# 401_GridPos4.net
KiCad netlist of a schematic drawn in Altium Designer
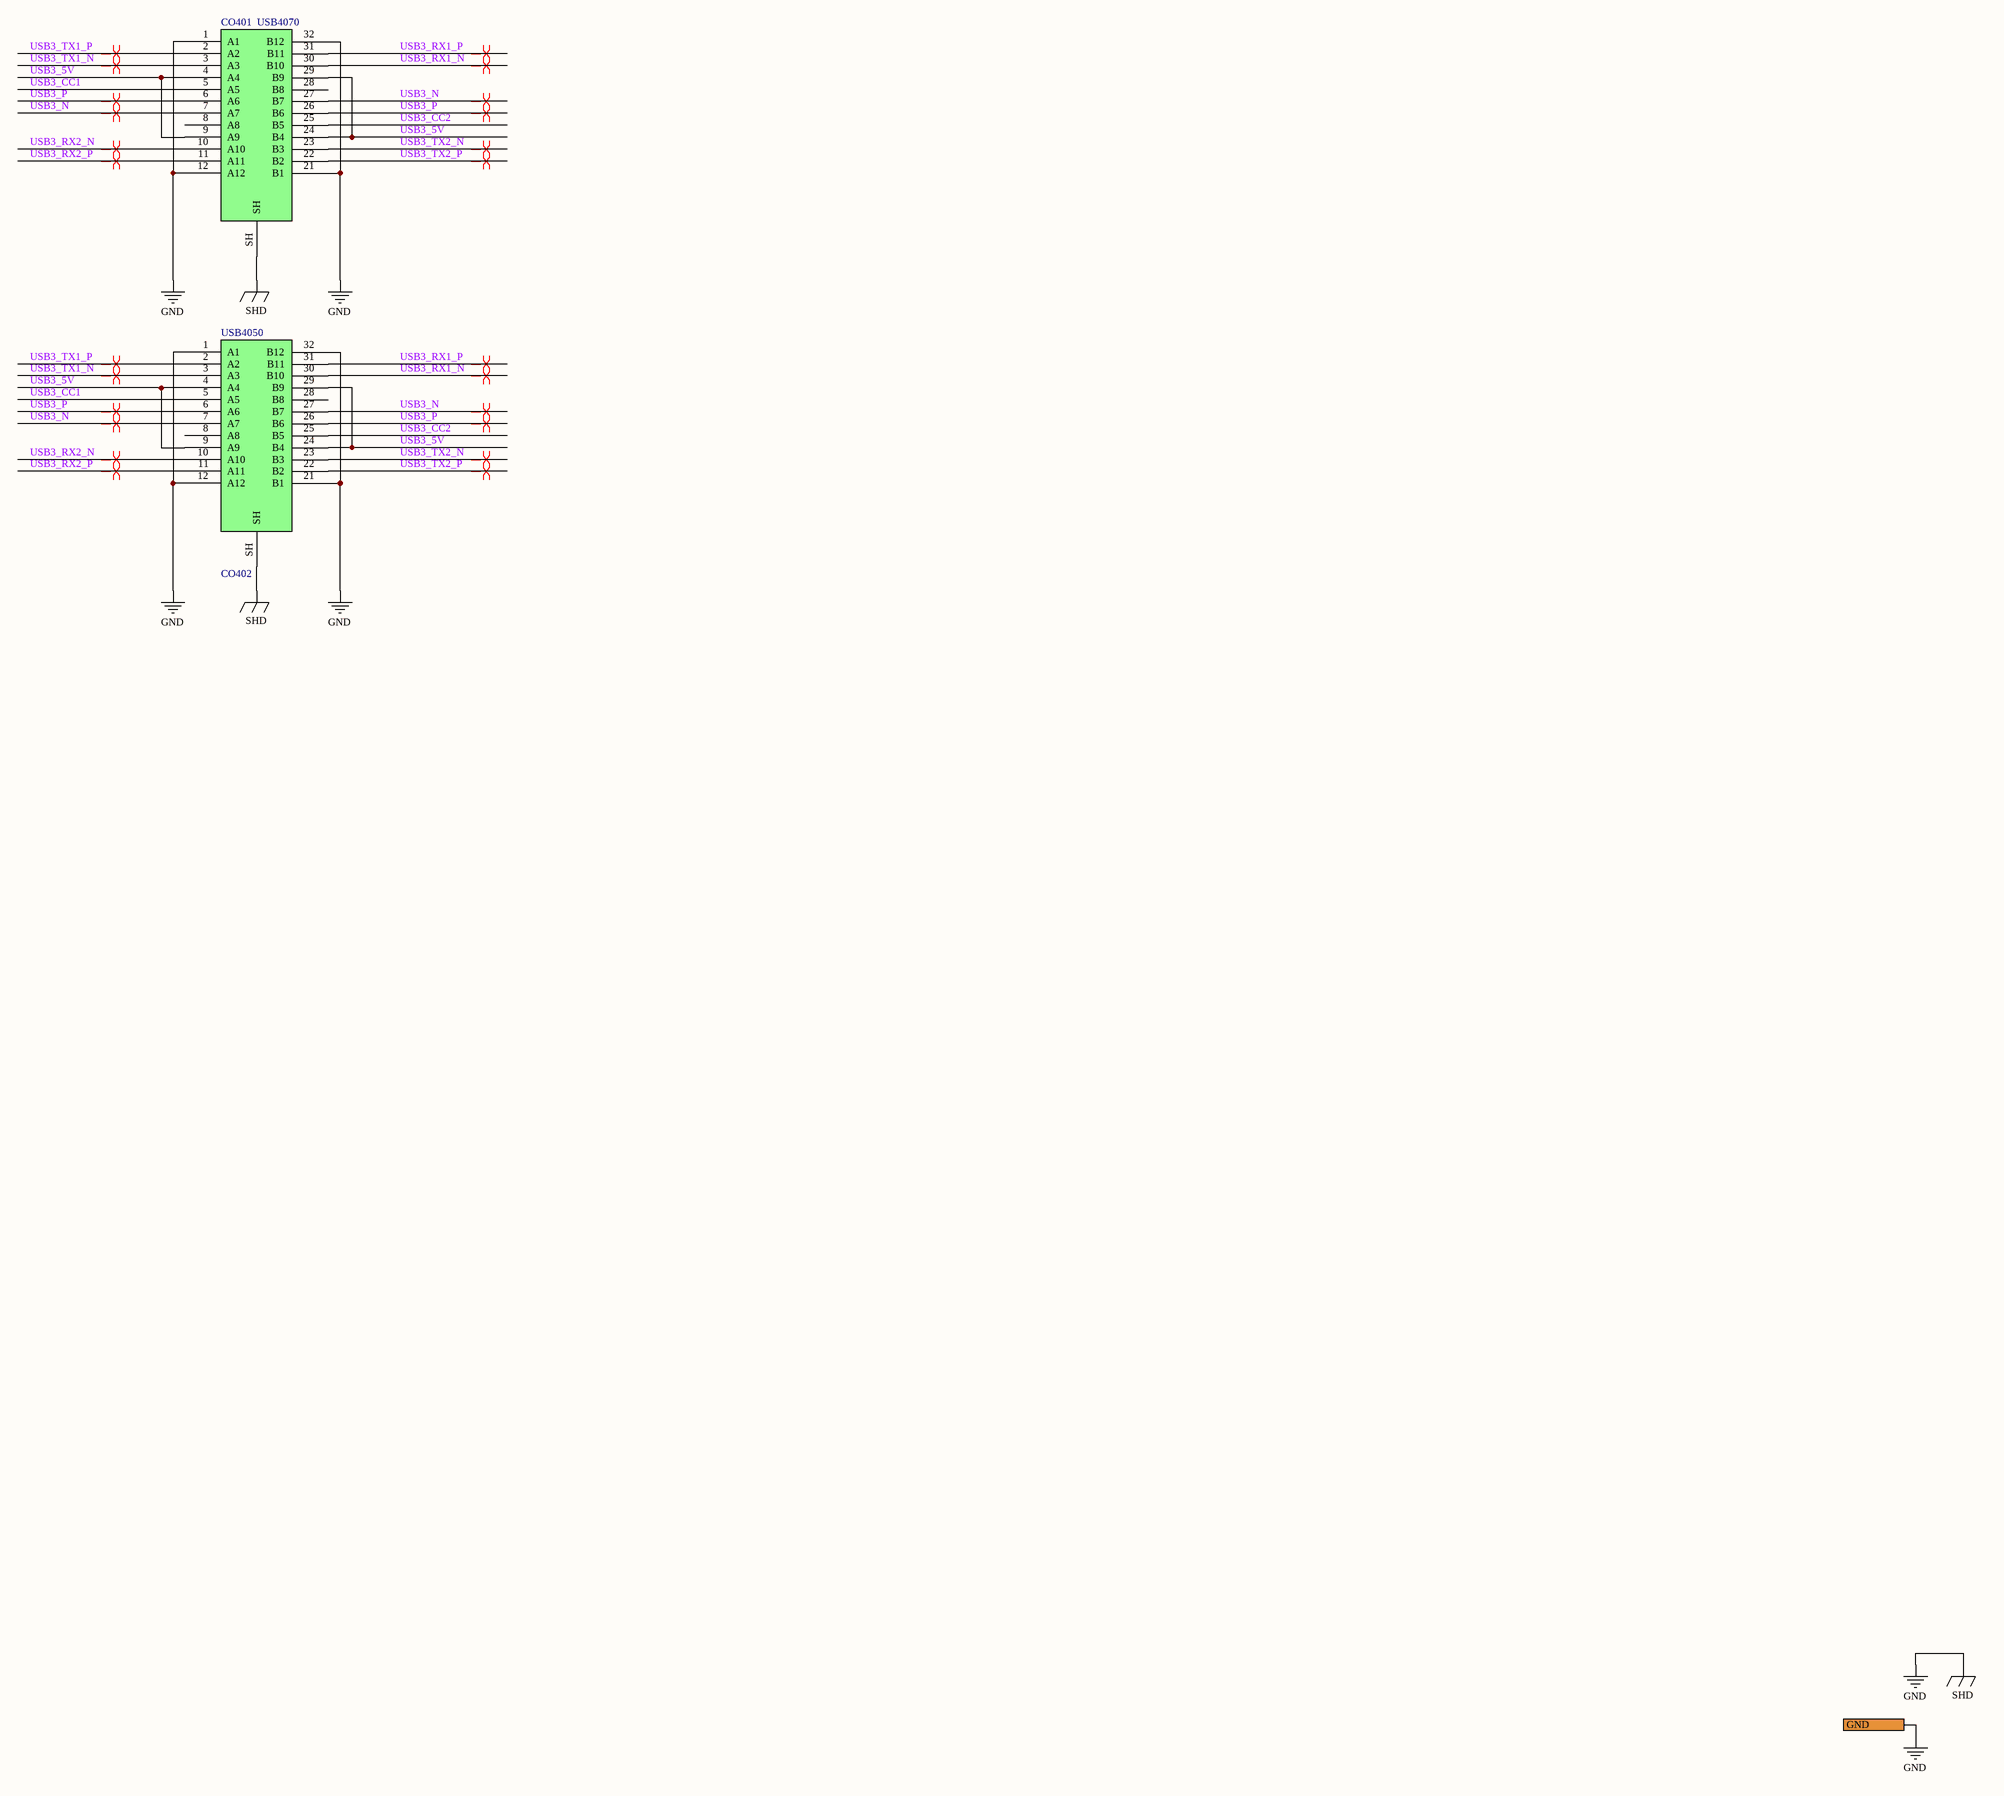
[diagram p0: 401_GridPos4.SchDoc]

(export (version "E")
  (design (tool "Eeschema 10.0.6"))
  (components
    (comp (ref "CO401")
      (value "USB4070")
      (footprint "USB4070-30-C")
      (description "USB4070-30-C")
      (fields (field (name "REFVAL") "USB4070") (field (name "PART NUMBER") "CO0021"))
      (libsource (lib "GTS_Database") (part "USB-CC"))
    )
    (comp (ref "CO402")
      (value "USB4050")
      (footprint "USB4050-30-A")
      (description "USB C connector Receptacle Horizontal")
      (fields
        (field (name "REFVAL") "USB4050")
        (field (name "PART NUMBER") "CO0039")
        (field (name "MANFACTPART") "USB4050-30-A")
      )
      (libsource (lib "") (part "USB-CC_1"))
    )
  )
  (nets
    (net (code "1") (name "/USB3_5V") (class "Default")
      (node (ref "CO401") (pin "24") (pinfunction "B4_24") (pintype "passive"))
      (node (ref "CO401") (pin "29") (pinfunction "B9_29") (pintype "passive"))
      (node (ref "CO401") (pin "4") (pinfunction "A4_4") (pintype "passive"))
      (node (ref "CO401") (pin "9") (pinfunction "A9_9") (pintype "passive"))
      (node (ref "CO402") (pin "24") (pinfunction "B4_24") (pintype "passive"))
      (node (ref "CO402") (pin "29") (pinfunction "B9_29") (pintype "passive"))
      (node (ref "CO402") (pin "4") (pinfunction "A4_4") (pintype "passive"))
      (node (ref "CO402") (pin "9") (pinfunction "A9_9") (pintype "passive"))
    )
    (net (code "2") (name "/USB3_CC1") (class "Default")
      (node (ref "CO401") (pin "5") (pinfunction "A5_5") (pintype "passive"))
      (node (ref "CO402") (pin "5") (pinfunction "A5_5") (pintype "passive"))
    )
    (net (code "3") (name "/USB3_CC2") (class "Default")
      (node (ref "CO401") (pin "25") (pinfunction "B5_25") (pintype "passive"))
      (node (ref "CO402") (pin "25") (pinfunction "B5_25") (pintype "passive"))
    )
    (net (code "4") (name "/USB3_N") (class "Default")
      (node (ref "CO401") (pin "27") (pinfunction "B7_27") (pintype "passive"))
      (node (ref "CO401") (pin "7") (pinfunction "A7_7") (pintype "passive"))
      (node (ref "CO402") (pin "27") (pinfunction "B7_27") (pintype "passive"))
      (node (ref "CO402") (pin "7") (pinfunction "A7_7") (pintype "passive"))
    )
    (net (code "5") (name "/USB3_P") (class "Default")
      (node (ref "CO401") (pin "26") (pinfunction "B6_26") (pintype "passive"))
      (node (ref "CO401") (pin "6") (pinfunction "A6_6") (pintype "passive"))
      (node (ref "CO402") (pin "26") (pinfunction "B6_26") (pintype "passive"))
      (node (ref "CO402") (pin "6") (pinfunction "A6_6") (pintype "passive"))
    )
    (net (code "6") (name "/USB3_RX1_N") (class "Default")
      (node (ref "CO401") (pin "30") (pinfunction "B10_30") (pintype "passive"))
      (node (ref "CO402") (pin "30") (pinfunction "B10_30") (pintype "passive"))
    )
    (net (code "7") (name "/USB3_RX1_P") (class "Default")
      (node (ref "CO401") (pin "31") (pinfunction "B11_31") (pintype "passive"))
      (node (ref "CO402") (pin "31") (pinfunction "B11_31") (pintype "passive"))
    )
    (net (code "8") (name "/USB3_RX2_N") (class "Default")
      (node (ref "CO401") (pin "10") (pinfunction "A10_10") (pintype "passive"))
      (node (ref "CO402") (pin "10") (pinfunction "A10_10") (pintype "passive"))
    )
    (net (code "9") (name "/USB3_RX2_P") (class "Default")
      (node (ref "CO401") (pin "11") (pinfunction "A11_11") (pintype "passive"))
      (node (ref "CO402") (pin "11") (pinfunction "A11_11") (pintype "passive"))
    )
    (net (code "10") (name "/USB3_TX1_N") (class "Default")
      (node (ref "CO401") (pin "3") (pinfunction "A3_3") (pintype "passive"))
      (node (ref "CO402") (pin "3") (pinfunction "A3_3") (pintype "passive"))
    )
    (net (code "11") (name "/USB3_TX1_P") (class "Default")
      (node (ref "CO401") (pin "2") (pinfunction "A2_2") (pintype "passive"))
      (node (ref "CO402") (pin "2") (pinfunction "A2_2") (pintype "passive"))
    )
    (net (code "12") (name "/USB3_TX2_N") (class "Default")
      (node (ref "CO401") (pin "23") (pinfunction "B3_23") (pintype "passive"))
      (node (ref "CO402") (pin "23") (pinfunction "B3_23") (pintype "passive"))
    )
    (net (code "13") (name "/USB3_TX2_P") (class "Default")
      (node (ref "CO401") (pin "22") (pinfunction "B2_22") (pintype "passive"))
      (node (ref "CO402") (pin "22") (pinfunction "B2_22") (pintype "passive"))
    )
    (net (code "14") (name "GND") (class "Default")
      (node (ref "CO401") (pin "1") (pinfunction "A1_1") (pintype "passive"))
      (node (ref "CO401") (pin "12") (pinfunction "A12_12") (pintype "passive"))
      (node (ref "CO401") (pin "21") (pinfunction "B1_21") (pintype "passive"))
      (node (ref "CO401") (pin "32") (pinfunction "B12_32") (pintype "passive"))
      (node (ref "CO401") (pin "SH") (pinfunction "SH_SH") (pintype "power_in"))
      (node (ref "CO402") (pin "1") (pinfunction "A1_1") (pintype "passive"))
      (node (ref "CO402") (pin "12") (pinfunction "A12_12") (pintype "passive"))
      (node (ref "CO402") (pin "21") (pinfunction "B1_21") (pintype "passive"))
      (node (ref "CO402") (pin "32") (pinfunction "B12_32") (pintype "passive"))
      (node (ref "CO402") (pin "SH") (pinfunction "SH_SH") (pintype "power_in"))
    )
    (net (code "15") (name "unconnected-(CO401-A8-Pad8)") (class "Default")
      (node (ref "CO401") (pin "8") (pinfunction "A8_8") (pintype "passive"))
    )
    (net (code "16") (name "unconnected-(CO401-B8-Pad28)") (class "Default")
      (node (ref "CO401") (pin "28") (pinfunction "B8_28") (pintype "passive"))
    )
    (net (code "17") (name "unconnected-(CO402-A8-Pad8)") (class "Default")
      (node (ref "CO402") (pin "8") (pinfunction "A8_8") (pintype "passive"))
    )
    (net (code "18") (name "unconnected-(CO402-B8-Pad28)") (class "Default")
      (node (ref "CO402") (pin "28") (pinfunction "B8_28") (pintype "passive"))
    )
  )
)
